# PT100.net
KiCad netlist of a schematic drawn in Altium Designer
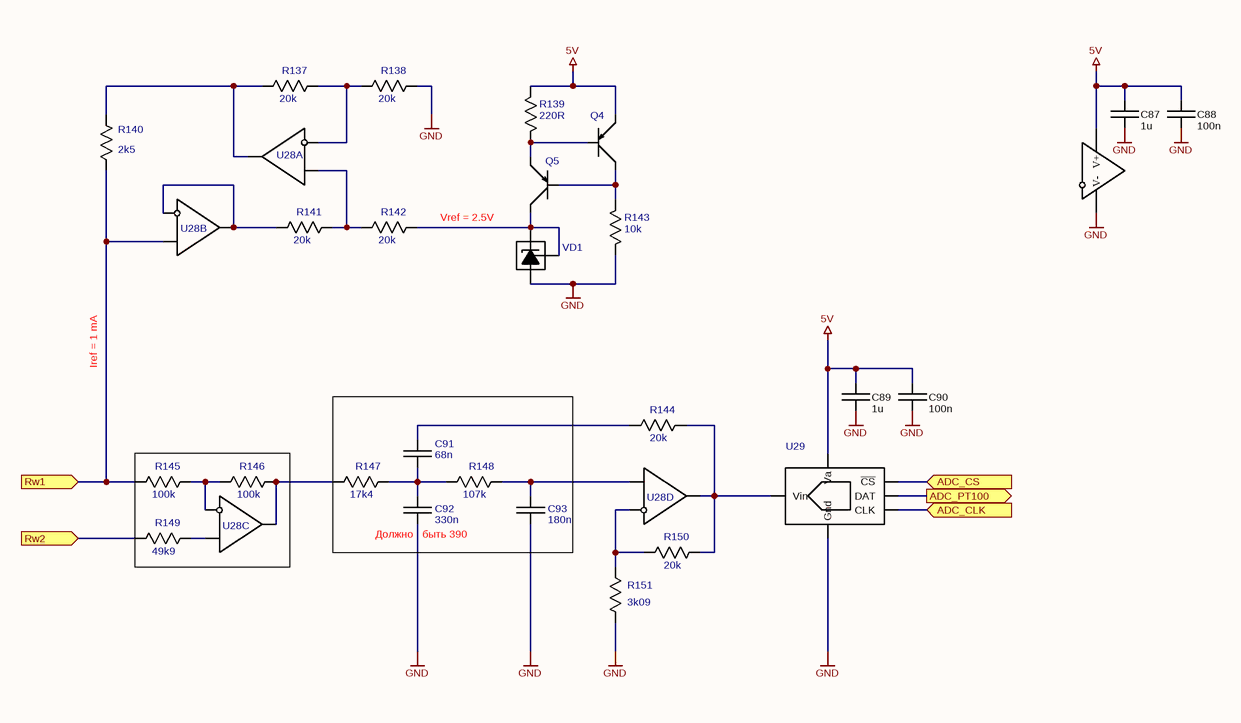
[diagram p0: PT100.SchDoc]

(export (version "E")
  (design (tool "Eeschema 10.0.6"))
  (components
    (comp (ref "C87")
      (value "1u")
      (footprint "levin:CAP CER 0603 NP")
      (description "CC0603KRX5R7BB105")
      (libsource (lib "levin") (part "Capacitor"))
    )
    (comp (ref "C88")
      (value "100n")
      (footprint "levin:CAP CER 0603 NP")
      (description "CC0603KRX7R9BB104")
      (libsource (lib "levin") (part "Capacitor"))
    )
    (comp (ref "C89")
      (value "1u")
      (footprint "levin:CAP CER 0603 NP")
      (description "CC0603KRX5R7BB105")
      (libsource (lib "levin") (part "Capacitor"))
    )
    (comp (ref "C90")
      (value "100n")
      (footprint "levin:CAP CER 0603 NP")
      (description "CC0603KRX7R9BB104")
      (libsource (lib "levin") (part "Capacitor"))
    )
    (comp (ref "C91")
      (value "68n")
      (footprint "levin:CAP CER 0603 NP")
      (description "CC0603JRX7R9BB683")
      (libsource (lib "levin") (part "Capacitor"))
    )
    (comp (ref "C92")
      (value "330n")
      (footprint "levin:CAP CER 0603 NP")
      (description "CC0603KRX5R8BB334")
      (libsource (lib "levin") (part "Capacitor"))
    )
    (comp (ref "C93")
      (value "180n")
      (footprint "levin:CAP CER 0603 NP")
      (description "GRM188R71E184KA88D")
      (libsource (lib "levin") (part "Capacitor"))
    )
    (comp (ref "Q4")
      (value "PNP Bipolar Transistor")
      (footprint "levin:SOT-23")
      (description "BC857")
      (libsource (lib "levin") (part "Bipolar PNP"))
    )
    (comp (ref "Q5")
      (value "PNP Bipolar Transistor")
      (footprint "levin:SOT-23")
      (description "BC857")
      (libsource (lib "levin") (part "Bipolar PNP"))
    )
    (comp (ref "R137")
      (value "20k")
      (footprint "levin:RES 0603")
      (description "RT0603BRD0720KL")
      (libsource (lib "levin") (part "Resistor"))
    )
    (comp (ref "R138")
      (value "20k")
      (footprint "levin:RES 0603")
      (description "RT0603BRD0720KL")
      (libsource (lib "levin") (part "Resistor"))
    )
    (comp (ref "R139")
      (value "220R")
      (footprint "levin:RES 0603")
      (description "RT0603BRD07220RL")
      (libsource (lib "levin") (part "Resistor"))
    )
    (comp (ref "R140")
      (value "2k5")
      (footprint "levin:RES 0603")
      (description "AR03BTC2501")
      (libsource (lib "levin") (part "Resistor"))
    )
    (comp (ref "R141")
      (value "20k")
      (footprint "levin:RES 0603")
      (description "RT0603BRD0720KL")
      (libsource (lib "levin") (part "Resistor"))
    )
    (comp (ref "R142")
      (value "20k")
      (footprint "levin:RES 0603")
      (description "RT0603BRD0720KL")
      (libsource (lib "levin") (part "Resistor"))
    )
    (comp (ref "R143")
      (value "10k")
      (footprint "levin:RES 0603")
      (description "RT0603BRD0710KL")
      (libsource (lib "levin") (part "Resistor"))
    )
    (comp (ref "R144")
      (value "20k")
      (footprint "levin:RES 0603")
      (description "RC0603FR-0720KL")
      (libsource (lib "levin") (part "Resistor"))
    )
    (comp (ref "R145")
      (value "100k")
      (footprint "levin:RES 0603")
      (description "RC0603FR-07100KL")
      (libsource (lib "levin") (part "Resistor"))
    )
    (comp (ref "R146")
      (value "100k")
      (footprint "levin:RES 0603")
      (description "RC0603FR-07100KL")
      (libsource (lib "levin") (part "Resistor"))
    )
    (comp (ref "R147")
      (value "17k4")
      (footprint "levin:RES 0603")
      (description "RC0603FR-0717K4L")
      (libsource (lib "levin") (part "Resistor"))
    )
    (comp (ref "R148")
      (value "107k")
      (footprint "levin:RES 0603")
      (description "RC0603FR-07107KL")
      (libsource (lib "levin") (part "Resistor"))
    )
    (comp (ref "R149")
      (value "49k9")
      (footprint "levin:RES 0603")
      (description "RC0603FR-0749K9L")
      (libsource (lib "levin") (part "Resistor"))
    )
    (comp (ref "R150")
      (value "20k")
      (footprint "levin:RES 0603")
      (description "RC0603FR-0720KL")
      (libsource (lib "levin") (part "Resistor"))
    )
    (comp (ref "R151")
      (value "3k09")
      (footprint "levin:RES 0603")
      (description "RC0603FR-073K09L")
      (libsource (lib "levin") (part "Resistor"))
    )
    (comp (ref "U28")
      (value "OpAmp x4 Small")
      (footprint "levin:SOIC-14")
      (description "LMV324IDT")
      (libsource (lib "") (part "OpAmp x4 Small_2"))
    )
    (comp (ref "U29")
      (value "SAR ADC")
      (footprint "levin:SOT-23-6")
      (description "ADC121S021CIMF")
      (libsource (lib "levin") (part "ADC121"))
    )
    (comp (ref "VD1")
      (value "Zenner Diode Adjustable")
      (footprint "levin:SOT-23")
      (description "TL431ACDBZR")
      (libsource (lib "levin") (part "TL431"))
    )
  )
  (nets
    (net (code "1") (name "/ADC_CLK") (class "Default")
      (node (ref "U29") (pin "4") (pinfunction "CLK_4") (pintype "passive"))
    )
    (net (code "2") (name "/ADC_CS") (class "Default")
      (node (ref "U29") (pin "6") (pinfunction "~{CS}_6") (pintype "passive"))
    )
    (net (code "3") (name "/ADC_PT100") (class "Default")
      (node (ref "U29") (pin "5") (pinfunction "DAT_5") (pintype "passive"))
    )
    (net (code "4") (name "/Rw1") (class "Default")
      (node (ref "R140") (pin "1") (pinfunction "1_1") (pintype "passive"))
      (node (ref "R145") (pin "1") (pinfunction "1_1") (pintype "passive"))
      (node (ref "U28") (pin "4") (pinfunction "+IN_4") (pintype "passive"))
    )
    (net (code "5") (name "/Rw2") (class "Default")
      (node (ref "R149") (pin "1") (pinfunction "1_1") (pintype "passive"))
    )
    (net (code "6") (name "5V") (class "Default")
      (node (ref "C87") (pin "1") (pinfunction "1_1") (pintype "passive"))
      (node (ref "C88") (pin "1") (pinfunction "1_1") (pintype "passive"))
      (node (ref "C89") (pin "1") (pinfunction "1_1") (pintype "passive"))
      (node (ref "C90") (pin "1") (pinfunction "1_1") (pintype "passive"))
      (node (ref "Q4") (pin "2") (pinfunction "E_2") (pintype "passive"))
      (node (ref "R139") (pin "2") (pinfunction "2_2") (pintype "passive"))
      (node (ref "U28") (pin "13") (pinfunction "V+_13") (pintype "passive"))
      (node (ref "U29") (pin "1") (pinfunction "Va_1") (pintype "passive"))
    )
    (net (code "7") (name "GND") (class "Default")
      (node (ref "C87") (pin "2") (pinfunction "2_2") (pintype "passive"))
      (node (ref "C88") (pin "2") (pinfunction "2_2") (pintype "passive"))
      (node (ref "C89") (pin "2") (pinfunction "2_2") (pintype "passive"))
      (node (ref "C90") (pin "2") (pinfunction "2_2") (pintype "passive"))
      (node (ref "C92") (pin "1") (pinfunction "1_1") (pintype "passive"))
      (node (ref "C93") (pin "1") (pinfunction "1_1") (pintype "passive"))
      (node (ref "R138") (pin "2") (pinfunction "2_2") (pintype "passive"))
      (node (ref "R143") (pin "1") (pinfunction "1_1") (pintype "passive"))
      (node (ref "R151") (pin "1") (pinfunction "1_1") (pintype "passive"))
      (node (ref "U28") (pin "14") (pinfunction "V-_14") (pintype "passive"))
      (node (ref "U29") (pin "2") (pinfunction "Gnd_2") (pintype "passive"))
      (node (ref "VD1") (pin "1") (pinfunction "A_1") (pintype "passive"))
    )
    (net (code "8") (name "Net-(C91-Pad1)") (class "Default")
      (node (ref "C91") (pin "1") (pinfunction "1_1") (pintype "passive"))
      (node (ref "C92") (pin "2") (pinfunction "2_2") (pintype "passive"))
      (node (ref "R147") (pin "2") (pinfunction "2_2") (pintype "passive"))
      (node (ref "R148") (pin "1") (pinfunction "1_1") (pintype "passive"))
    )
    (net (code "9") (name "Net-(C91-Pad2)") (class "Default")
      (node (ref "C91") (pin "2") (pinfunction "2_2") (pintype "passive"))
      (node (ref "R144") (pin "1") (pinfunction "1_1") (pintype "passive"))
    )
    (net (code "10") (name "Net-(Q4-B)") (class "Default")
      (node (ref "Q4") (pin "1") (pinfunction "B_1") (pintype "passive"))
      (node (ref "Q5") (pin "2") (pinfunction "E_2") (pintype "passive"))
      (node (ref "R139") (pin "1") (pinfunction "1_1") (pintype "passive"))
    )
    (net (code "11") (name "Net-(Q4-C)") (class "Default")
      (node (ref "Q4") (pin "3") (pinfunction "C_3") (pintype "passive"))
      (node (ref "Q5") (pin "1") (pinfunction "B_1") (pintype "passive"))
      (node (ref "R143") (pin "2") (pinfunction "2_2") (pintype "passive"))
    )
    (net (code "12") (name "Net-(Q5-C)") (class "Default")
      (node (ref "Q5") (pin "3") (pinfunction "C_3") (pintype "passive"))
      (node (ref "R142") (pin "2") (pinfunction "2_2") (pintype "passive"))
      (node (ref "VD1") (pin "2") (pinfunction "C_2") (pintype "passive"))
      (node (ref "VD1") (pin "3") (pinfunction "Ref_3") (pintype "passive"))
    )
    (net (code "13") (name "Net-(U28A-+IN1)") (class "Default")
      (node (ref "R141") (pin "2") (pinfunction "2_2") (pintype "passive"))
      (node (ref "R142") (pin "1") (pinfunction "1_1") (pintype "passive"))
      (node (ref "U28") (pin "1") (pinfunction "+IN1_1") (pintype "passive"))
    )
    (net (code "14") (name "Net-(U28A--IN1)") (class "Default")
      (node (ref "R137") (pin "2") (pinfunction "2_2") (pintype "passive"))
      (node (ref "R138") (pin "1") (pinfunction "1_1") (pintype "passive"))
      (node (ref "U28") (pin "2") (pinfunction "-IN1_2") (pintype "passive"))
    )
    (net (code "15") (name "Net-(U28A-OUT1)") (class "Default")
      (node (ref "R137") (pin "1") (pinfunction "1_1") (pintype "passive"))
      (node (ref "R140") (pin "2") (pinfunction "2_2") (pintype "passive"))
      (node (ref "U28") (pin "3") (pinfunction "OUT1_3") (pintype "passive"))
    )
    (net (code "16") (name "Net-(U28B--IN)") (class "Default")
      (node (ref "R141") (pin "1") (pinfunction "1_1") (pintype "passive"))
      (node (ref "U28") (pin "5") (pinfunction "-IN_5") (pintype "passive"))
      (node (ref "U28") (pin "6") (pinfunction "OUT_6") (pintype "passive"))
    )
    (net (code "17") (name "Net-(U28C-+IN)") (class "Default")
      (node (ref "R149") (pin "2") (pinfunction "2_2") (pintype "passive"))
      (node (ref "U28") (pin "7") (pinfunction "+IN_7") (pintype "passive"))
    )
    (net (code "18") (name "Net-(U28C--IN)") (class "Default")
      (node (ref "R145") (pin "2") (pinfunction "2_2") (pintype "passive"))
      (node (ref "R146") (pin "1") (pinfunction "1_1") (pintype "passive"))
      (node (ref "U28") (pin "8") (pinfunction "-IN_8") (pintype "passive"))
    )
    (net (code "19") (name "Net-(U28C-OUT)") (class "Default")
      (node (ref "R146") (pin "2") (pinfunction "2_2") (pintype "passive"))
      (node (ref "R147") (pin "1") (pinfunction "1_1") (pintype "passive"))
      (node (ref "U28") (pin "9") (pinfunction "OUT_9") (pintype "passive"))
    )
    (net (code "20") (name "Net-(U28D-+IN)") (class "Default")
      (node (ref "C93") (pin "2") (pinfunction "2_2") (pintype "passive"))
      (node (ref "R148") (pin "2") (pinfunction "2_2") (pintype "passive"))
      (node (ref "U28") (pin "10") (pinfunction "+IN_10") (pintype "passive"))
    )
    (net (code "21") (name "Net-(U28D--IN)") (class "Default")
      (node (ref "R150") (pin "1") (pinfunction "1_1") (pintype "passive"))
      (node (ref "R151") (pin "2") (pinfunction "2_2") (pintype "passive"))
      (node (ref "U28") (pin "11") (pinfunction "-IN_11") (pintype "passive"))
    )
    (net (code "22") (name "Net-(U28D-OUT)") (class "Default")
      (node (ref "R144") (pin "2") (pinfunction "2_2") (pintype "passive"))
      (node (ref "R150") (pin "2") (pinfunction "2_2") (pintype "passive"))
      (node (ref "U28") (pin "12") (pinfunction "OUT_12") (pintype "passive"))
      (node (ref "U29") (pin "3") (pinfunction "Vin_3") (pintype "passive"))
    )
  )
)
